# F1-chip.net
KiCad netlist of a schematic drawn in Altium Designer
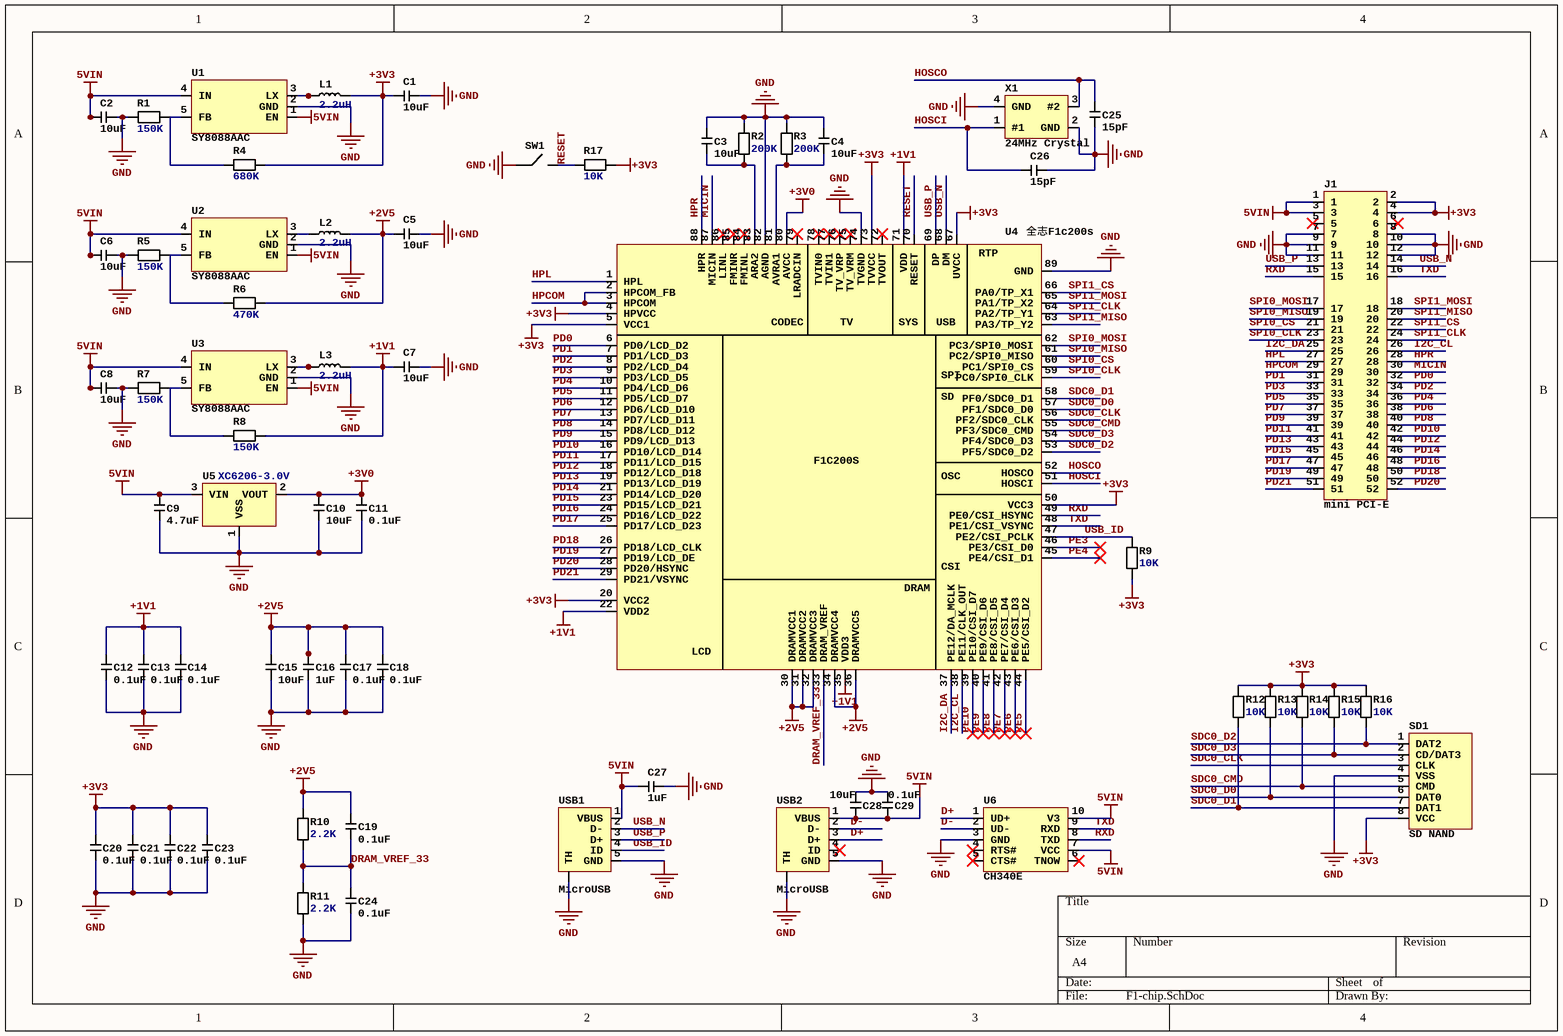
[diagram p0: F1-chip.SchDoc]

(export (version "E")
  (design (tool "Eeschema 10.0.6"))
  (components
    (comp (ref "C1")
      (value "10uF")
      (footprint "CAP_0402")
      (description "0402")
      (libsource (lib "myIntlib") (part "CAP_0402_10uF"))
    )
    (comp (ref "C2")
      (value "10uF")
      (footprint "CAP_0402")
      (description "0402")
      (libsource (lib "myIntlib") (part "CAP_0402_10uF"))
    )
    (comp (ref "C3")
      (value "10uF")
      (footprint "CAP_0402")
      (description "0402")
      (libsource (lib "myIntlib") (part "CAP_0402_10uF"))
    )
    (comp (ref "C4")
      (value "10uF")
      (footprint "CAP_0402")
      (description "0402")
      (libsource (lib "myIntlib") (part "CAP_0402_10uF"))
    )
    (comp (ref "C5")
      (value "10uF")
      (footprint "CAP_0402")
      (description "0402")
      (libsource (lib "myIntlib") (part "CAP_0402_10uF"))
    )
    (comp (ref "C6")
      (value "10uF")
      (footprint "CAP_0402")
      (description "0402")
      (libsource (lib "myIntlib") (part "CAP_0402_10uF"))
    )
    (comp (ref "C7")
      (value "10uF")
      (footprint "CAP_0402")
      (description "0402")
      (libsource (lib "myIntlib") (part "CAP_0402_10uF"))
    )
    (comp (ref "C8")
      (value "10uF")
      (footprint "CAP_0402")
      (description "0402")
      (libsource (lib "myIntlib") (part "CAP_0402_10uF"))
    )
    (comp (ref "C9")
      (value "4.7uF")
      (footprint "CAP_0402")
      (description "0402")
      (libsource (lib "myIntlib") (part "CAP_0402_4.7uF"))
    )
    (comp (ref "C10")
      (value "10uF")
      (footprint "CAP_0402")
      (description "0402")
      (libsource (lib "myIntlib") (part "CAP_0402_10uF"))
    )
    (comp (ref "C11")
      (value "0.1uF")
      (footprint "CAP_0402")
      (description "0402")
      (libsource (lib "myIntlib") (part "CAP_0402_0.1uF"))
    )
    (comp (ref "C12")
      (value "0.1uF")
      (footprint "CAP_0402")
      (description "0402")
      (libsource (lib "myIntlib") (part "CAP_0402_0.1uF"))
    )
    (comp (ref "C13")
      (value "0.1uF")
      (footprint "CAP_0402")
      (description "0402")
      (libsource (lib "myIntlib") (part "CAP_0402_0.1uF"))
    )
    (comp (ref "C14")
      (value "0.1uF")
      (footprint "CAP_0402")
      (description "0402")
      (libsource (lib "myIntlib") (part "CAP_0402_0.1uF"))
    )
    (comp (ref "C15")
      (value "10uF")
      (footprint "CAP_0402")
      (description "0402")
      (libsource (lib "myIntlib") (part "CAP_0402_10uF"))
    )
    (comp (ref "C16")
      (value "1uF")
      (footprint "CAP_0402")
      (description "0402")
      (libsource (lib "myIntlib") (part "CAP_0402_1uF"))
    )
    (comp (ref "C17")
      (value "0.1uF")
      (footprint "CAP_0402")
      (description "0402")
      (libsource (lib "myIntlib") (part "CAP_0402_0.1uF"))
    )
    (comp (ref "C18")
      (value "0.1uF")
      (footprint "CAP_0402")
      (description "0402")
      (libsource (lib "myIntlib") (part "CAP_0402_0.1uF"))
    )
    (comp (ref "C19")
      (value "0.1uF")
      (footprint "CAP_0402")
      (description "0402")
      (libsource (lib "myIntlib") (part "CAP_0402_0.1uF"))
    )
    (comp (ref "C20")
      (value "0.1uF")
      (footprint "CAP_0402")
      (description "0402")
      (libsource (lib "myIntlib") (part "CAP_0402_0.1uF"))
    )
    (comp (ref "C21")
      (value "0.1uF")
      (footprint "CAP_0402")
      (description "0402")
      (libsource (lib "myIntlib") (part "CAP_0402_0.1uF"))
    )
    (comp (ref "C22")
      (value "0.1uF")
      (footprint "CAP_0402")
      (description "0402")
      (libsource (lib "myIntlib") (part "CAP_0402_0.1uF"))
    )
    (comp (ref "C23")
      (value "0.1uF")
      (footprint "CAP_0402")
      (description "0402")
      (libsource (lib "myIntlib") (part "CAP_0402_0.1uF"))
    )
    (comp (ref "C24")
      (value "0.1uF")
      (footprint "CAP_0402")
      (description "0402")
      (libsource (lib "myIntlib") (part "CAP_0402_0.1uF"))
    )
    (comp (ref "C25")
      (value "15pF")
      (footprint "CAP_0402")
      (description "0402")
      (libsource (lib "myIntlib") (part "CAP_0402_15pF"))
    )
    (comp (ref "C26")
      (value "15pF")
      (footprint "CAP_0402")
      (description "0402")
      (libsource (lib "myIntlib") (part "CAP_0402_15pF"))
    )
    (comp (ref "C27")
      (value "1uF")
      (footprint "CAP_0402")
      (description "0402")
      (libsource (lib "myIntlib") (part "CAP_0402_1uF"))
    )
    (comp (ref "C28")
      (value "10uF")
      (footprint "CAP_0402")
      (description "0402")
      (libsource (lib "myIntlib") (part "CAP_0402_10uF"))
    )
    (comp (ref "C29")
      (value "0.1uF")
      (footprint "CAP_0402")
      (description "0402")
      (libsource (lib "myIntlib") (part "CAP_0402_0.1uF"))
    )
    (comp (ref "J1")
      (value "mini PCI-E")
      (footprint "mini PCI-E")
      (libsource (lib "myIntlib") (part "mini PCI-E"))
    )
    (comp (ref "L1")
      (value "2.2uH")
      (footprint "IND_0603")
      (description "0603")
      (libsource (lib "myIntlib") (part "IND_0603_2.2uH"))
    )
    (comp (ref "L2")
      (value "2.2uH")
      (footprint "IND_0603")
      (description "0603")
      (libsource (lib "myIntlib") (part "IND_0603_2.2uH"))
    )
    (comp (ref "L3")
      (value "2.2uH")
      (footprint "IND_0603")
      (description "0603")
      (libsource (lib "myIntlib") (part "IND_0603_2.2uH"))
    )
    (comp (ref "R1")
      (value "150K")
      (footprint "RES_0402")
      (description "0402")
      (libsource (lib "myIntlib") (part "RES_0402_150K"))
    )
    (comp (ref "R2")
      (value "200K")
      (footprint "RES_0402")
      (description "0402")
      (libsource (lib "myIntlib") (part "RES_0402_200K"))
    )
    (comp (ref "R3")
      (value "200K")
      (footprint "RES_0402")
      (description "0402")
      (libsource (lib "myIntlib") (part "RES_0402_200K"))
    )
    (comp (ref "R4")
      (value "680K")
      (footprint "RES_0402")
      (description "0402")
      (libsource (lib "myIntlib") (part "RES_0402_680K"))
    )
    (comp (ref "R5")
      (value "150K")
      (footprint "RES_0402")
      (description "0402")
      (libsource (lib "myIntlib") (part "RES_0402_150K"))
    )
    (comp (ref "R6")
      (value "470K")
      (footprint "RES_0402")
      (description "0402")
      (libsource (lib "myIntlib") (part "RES_0402_470K"))
    )
    (comp (ref "R7")
      (value "150K")
      (footprint "RES_0402")
      (description "0402")
      (libsource (lib "myIntlib") (part "RES_0402_150K"))
    )
    (comp (ref "R8")
      (value "150K")
      (footprint "RES_0402")
      (description "0402")
      (libsource (lib "myIntlib") (part "RES_0402_150K"))
    )
    (comp (ref "R9")
      (value "10K")
      (footprint "RES_0402")
      (description "0402")
      (libsource (lib "myIntlib") (part "RES_0402_10K"))
    )
    (comp (ref "R10")
      (value "2.2K")
      (footprint "RES_0402")
      (description "0402")
      (libsource (lib "myIntlib") (part "RES_0402_2.2K"))
    )
    (comp (ref "R11")
      (value "2.2K")
      (footprint "RES_0402")
      (description "0402")
      (libsource (lib "myIntlib") (part "RES_0402_2.2K"))
    )
    (comp (ref "R12")
      (value "10K")
      (footprint "RES_0402")
      (description "0402")
      (libsource (lib "myIntlib") (part "RES_0402_10K"))
    )
    (comp (ref "R13")
      (value "10K")
      (footprint "RES_0402")
      (description "0402")
      (libsource (lib "myIntlib") (part "RES_0402_10K"))
    )
    (comp (ref "R14")
      (value "10K")
      (footprint "RES_0402")
      (description "0402")
      (libsource (lib "myIntlib") (part "RES_0402_10K"))
    )
    (comp (ref "R15")
      (value "10K")
      (footprint "RES_0402")
      (description "0402")
      (libsource (lib "myIntlib") (part "RES_0402_10K"))
    )
    (comp (ref "R16")
      (value "10K")
      (footprint "RES_0402")
      (description "0402")
      (libsource (lib "myIntlib") (part "RES_0402_10K"))
    )
    (comp (ref "R17")
      (value "10K")
      (footprint "RES_0402")
      (description "0402")
      (libsource (lib "myIntlib") (part "RES_0402_10K"))
    )
    (comp (ref "SD1") (value "SD NAND") (footprint "SD NAND") (libsource (lib "myIntlib") (part "SD NAND")))
    (comp (ref "SW1")
      (value "贴片按钮")
      (footprint "BUTTON2")
      (description "3*4*2两脚小龟贴片按钮")
      (libsource (lib "myIntlib") (part "贴片按钮"))
    )
    (comp (ref "U1")
      (value "SY8088AAC")
      (footprint "SY8088AAC")
      (description "SOT23-5")
      (libsource (lib "myIntlib") (part "SY8088AAC"))
    )
    (comp (ref "U2")
      (value "SY8088AAC")
      (footprint "SY8088AAC")
      (description "SOT23-5")
      (libsource (lib "myIntlib") (part "SY8088AAC"))
    )
    (comp (ref "U3")
      (value "SY8088AAC")
      (footprint "SY8088AAC")
      (description "SOT23-5")
      (libsource (lib "myIntlib") (part "SY8088AAC"))
    )
    (comp (ref "U4")
      (value "全志F1c200s")
      (footprint "F1c200s")
      (description "MQFN-88")
      (libsource (lib "myIntlib") (part "F1c200s"))
    )
    (comp (ref "U5")
      (value "XC6206-3.0V")
      (footprint "XC6206")
      (description "SOT23-3")
      (libsource (lib "myIntlib") (part "XC6206-3.0V"))
    )
    (comp (ref "U6")
      (value "CH340E")
      (footprint "CH340E")
      (description "MSOP-10")
      (libsource (lib "myIntlib") (part "CH340E"))
    )
    (comp (ref "USB1")
      (value "MicroUSB")
      (footprint "MicroUSB")
      (libsource (lib "myIntlib") (part "MicroUSB"))
    )
    (comp (ref "USB2")
      (value "MicroUSB")
      (footprint "MicroUSB")
      (libsource (lib "myIntlib") (part "MicroUSB"))
    )
    (comp (ref "X1")
      (value "24MHz Crystal")
      (footprint "SMD3225")
      (description "SMD3225")
      (libsource (lib "myIntlib") (part "24MHz Crystal"))
    )
  )
  (nets
    (net (code "1") (name "+1V1") (class "Default")
      (node (ref "C12") (pin "2") (pinfunction "2_2") (pintype "passive"))
      (node (ref "C13") (pin "2") (pinfunction "2_2") (pintype "passive"))
      (node (ref "C14") (pin "2") (pinfunction "2_2") (pintype "passive"))
      (node (ref "C7") (pin "1") (pinfunction "1_1") (pintype "passive"))
      (node (ref "L3") (pin "2") (pinfunction "2_2") (pintype "passive"))
      (node (ref "R8") (pin "2") (pinfunction "2_2") (pintype "passive"))
      (node (ref "U4") (pin "22") (pinfunction "VDD2_22") (pintype "passive"))
      (node (ref "U4") (pin "35") (pinfunction "VDD3_35") (pintype "passive"))
      (node (ref "U4") (pin "71") (pinfunction "VDD_71") (pintype "passive"))
    )
    (net (code "2") (name "+2V5") (class "Default")
      (node (ref "C15") (pin "2") (pinfunction "2_2") (pintype "passive"))
      (node (ref "C16") (pin "2") (pinfunction "2_2") (pintype "passive"))
      (node (ref "C17") (pin "2") (pinfunction "2_2") (pintype "passive"))
      (node (ref "C18") (pin "2") (pinfunction "2_2") (pintype "passive"))
      (node (ref "C19") (pin "2") (pinfunction "2_2") (pintype "passive"))
      (node (ref "C5") (pin "1") (pinfunction "1_1") (pintype "passive"))
      (node (ref "L2") (pin "2") (pinfunction "2_2") (pintype "passive"))
      (node (ref "R10") (pin "2") (pinfunction "2_2") (pintype "passive"))
      (node (ref "R6") (pin "2") (pinfunction "2_2") (pintype "passive"))
      (node (ref "U4") (pin "30") (pinfunction "DRAMVCC1_30") (pintype "passive"))
      (node (ref "U4") (pin "31") (pinfunction "DRAMVCC2_31") (pintype "passive"))
      (node (ref "U4") (pin "32") (pinfunction "DRAMVCC3_32") (pintype "passive"))
      (node (ref "U4") (pin "34") (pinfunction "DRAMVCC4_34") (pintype "passive"))
      (node (ref "U4") (pin "36") (pinfunction "DRAMVCC5_36") (pintype "passive"))
    )
    (net (code "3") (name "+3V0") (class "Default")
      (node (ref "C10") (pin "2") (pinfunction "2_2") (pintype "passive"))
      (node (ref "C11") (pin "2") (pinfunction "2_2") (pintype "passive"))
      (node (ref "U4") (pin "80") (pinfunction "AVCC_80") (pintype "passive"))
      (node (ref "U5") (pin "2") (pinfunction "VOUT_2") (pintype "passive"))
    )
    (net (code "4") (name "+3V3") (class "Default")
      (node (ref "C1") (pin "1") (pinfunction "1_1") (pintype "passive"))
      (node (ref "C20") (pin "2") (pinfunction "2_2") (pintype "passive"))
      (node (ref "C21") (pin "2") (pinfunction "2_2") (pintype "passive"))
      (node (ref "C22") (pin "2") (pinfunction "2_2") (pintype "passive"))
      (node (ref "C23") (pin "2") (pinfunction "2_2") (pintype "passive"))
      (node (ref "J1") (pin "2") (pinfunction "2_2") (pintype "passive"))
      (node (ref "J1") (pin "4") (pinfunction "4_4") (pintype "passive"))
      (node (ref "L1") (pin "2") (pinfunction "2_2") (pintype "passive"))
      (node (ref "R12") (pin "2") (pinfunction "2_2") (pintype "passive"))
      (node (ref "R13") (pin "2") (pinfunction "2_2") (pintype "passive"))
      (node (ref "R14") (pin "2") (pinfunction "2_2") (pintype "passive"))
      (node (ref "R15") (pin "2") (pinfunction "2_2") (pintype "passive"))
      (node (ref "R16") (pin "2") (pinfunction "2_2") (pintype "passive"))
      (node (ref "R17") (pin "2") (pinfunction "2_2") (pintype "passive"))
      (node (ref "R4") (pin "2") (pinfunction "2_2") (pintype "passive"))
      (node (ref "R9") (pin "1") (pinfunction "1_1") (pintype "passive"))
      (node (ref "SD1") (pin "8") (pinfunction "VCC_8") (pintype "passive"))
      (node (ref "U4") (pin "20") (pinfunction "VCC2_20") (pintype "passive"))
      (node (ref "U4") (pin "4") (pinfunction "HPVCC_4") (pintype "passive"))
      (node (ref "U4") (pin "5") (pinfunction "VCC1_5") (pintype "passive"))
      (node (ref "U4") (pin "50") (pinfunction "VCC3_50") (pintype "passive"))
      (node (ref "U4") (pin "67") (pinfunction "UVCC_67") (pintype "passive"))
      (node (ref "U4") (pin "73") (pinfunction "TVVCC_73") (pintype "passive"))
    )
    (net (code "5") (name "/D+") (class "Default")
      (node (ref "U6") (pin "1") (pinfunction "UD+_1") (pintype "passive"))
      (node (ref "USB2") (pin "3") (pinfunction "D+_3") (pintype "passive"))
    )
    (net (code "6") (name "/D-") (class "Default")
      (node (ref "U6") (pin "2") (pinfunction "UD-_2") (pintype "passive"))
      (node (ref "USB2") (pin "2") (pinfunction "D-_2") (pintype "passive"))
    )
    (net (code "7") (name "/DRAM_VREF_33") (class "Default")
      (node (ref "C19") (pin "1") (pinfunction "1_1") (pintype "passive"))
      (node (ref "C24") (pin "2") (pinfunction "2_2") (pintype "passive"))
      (node (ref "R10") (pin "1") (pinfunction "1_1") (pintype "passive"))
      (node (ref "R11") (pin "2") (pinfunction "2_2") (pintype "passive"))
      (node (ref "U4") (pin "33") (pinfunction "DRAM_VREF_33") (pintype "passive"))
    )
    (net (code "8") (name "/HOSCI") (class "Default")
      (node (ref "C26") (pin "1") (pinfunction "1_1") (pintype "passive"))
      (node (ref "U4") (pin "51") (pinfunction "HOSCI_51") (pintype "passive"))
      (node (ref "X1") (pin "1") (pinfunction "#1_1") (pintype "passive"))
    )
    (net (code "9") (name "/HOSCO") (class "Default")
      (node (ref "C25") (pin "2") (pinfunction "2_2") (pintype "passive"))
      (node (ref "U4") (pin "52") (pinfunction "HOSCO_52") (pintype "passive"))
      (node (ref "X1") (pin "3") (pinfunction "#2_3") (pintype "passive"))
    )
    (net (code "10") (name "/HPCOM") (class "Default")
      (node (ref "J1") (pin "29") (pinfunction "29_29") (pintype "passive"))
      (node (ref "U4") (pin "2") (pinfunction "HPCOM_FB_2") (pintype "passive"))
      (node (ref "U4") (pin "3") (pinfunction "HPCOM_3") (pintype "passive"))
    )
    (net (code "11") (name "/HPL") (class "Default")
      (node (ref "J1") (pin "27") (pinfunction "27_27") (pintype "passive"))
      (node (ref "U4") (pin "1") (pinfunction "HPL_1") (pintype "passive"))
    )
    (net (code "12") (name "/HPR") (class "Default")
      (node (ref "J1") (pin "28") (pinfunction "28_28") (pintype "passive"))
      (node (ref "U4") (pin "88") (pinfunction "HPR_88") (pintype "passive"))
    )
    (net (code "13") (name "/I2C_CL") (class "Default")
      (node (ref "J1") (pin "26") (pinfunction "26_26") (pintype "passive"))
      (node (ref "U4") (pin "38") (pinfunction "PE11/CLK_OUT_38") (pintype "passive"))
    )
    (net (code "14") (name "/I2C_DA") (class "Default")
      (node (ref "J1") (pin "25") (pinfunction "25_25") (pintype "passive"))
      (node (ref "U4") (pin "37") (pinfunction "PE12/DA_MCLK_37") (pintype "passive"))
    )
    (net (code "15") (name "/MICIN") (class "Default")
      (node (ref "J1") (pin "30") (pinfunction "30_30") (pintype "passive"))
      (node (ref "U4") (pin "87") (pinfunction "MICIN_87") (pintype "passive"))
    )
    (net (code "16") (name "/PD0") (class "Default")
      (node (ref "J1") (pin "32") (pinfunction "32_32") (pintype "passive"))
      (node (ref "U4") (pin "6") (pinfunction "PD0/LCD_D2_6") (pintype "passive"))
    )
    (net (code "17") (name "/PD1") (class "Default")
      (node (ref "J1") (pin "31") (pinfunction "31_31") (pintype "passive"))
      (node (ref "U4") (pin "7") (pinfunction "PD1/LCD_D3_7") (pintype "passive"))
    )
    (net (code "18") (name "/PD2") (class "Default")
      (node (ref "J1") (pin "34") (pinfunction "34_34") (pintype "passive"))
      (node (ref "U4") (pin "8") (pinfunction "PD2/LCD_D4_8") (pintype "passive"))
    )
    (net (code "19") (name "/PD3") (class "Default")
      (node (ref "J1") (pin "33") (pinfunction "33_33") (pintype "passive"))
      (node (ref "U4") (pin "9") (pinfunction "PD3/LCD_D5_9") (pintype "passive"))
    )
    (net (code "20") (name "/PD4") (class "Default")
      (node (ref "J1") (pin "36") (pinfunction "36_36") (pintype "passive"))
      (node (ref "U4") (pin "10") (pinfunction "PD4/LCD_D6_10") (pintype "passive"))
    )
    (net (code "21") (name "/PD5") (class "Default")
      (node (ref "J1") (pin "35") (pinfunction "35_35") (pintype "passive"))
      (node (ref "U4") (pin "11") (pinfunction "PD5/LCD_D7_11") (pintype "passive"))
    )
    (net (code "22") (name "/PD6") (class "Default")
      (node (ref "J1") (pin "38") (pinfunction "38_38") (pintype "passive"))
      (node (ref "U4") (pin "12") (pinfunction "PD6/LCD_D10_12") (pintype "passive"))
    )
    (net (code "23") (name "/PD7") (class "Default")
      (node (ref "J1") (pin "37") (pinfunction "37_37") (pintype "passive"))
      (node (ref "U4") (pin "13") (pinfunction "PD7/LCD_D11_13") (pintype "passive"))
    )
    (net (code "24") (name "/PD8") (class "Default")
      (node (ref "J1") (pin "40") (pinfunction "40_40") (pintype "passive"))
      (node (ref "U4") (pin "14") (pinfunction "PD8/LCD_D12_14") (pintype "passive"))
    )
    (net (code "25") (name "/PD9") (class "Default")
      (node (ref "J1") (pin "39") (pinfunction "39_39") (pintype "passive"))
      (node (ref "U4") (pin "15") (pinfunction "PD9/LCD_D13_15") (pintype "passive"))
    )
    (net (code "26") (name "/PD10") (class "Default")
      (node (ref "J1") (pin "42") (pinfunction "42_42") (pintype "passive"))
      (node (ref "U4") (pin "16") (pinfunction "PD10/LCD_D14_16") (pintype "passive"))
    )
    (net (code "27") (name "/PD11") (class "Default")
      (node (ref "J1") (pin "41") (pinfunction "41_41") (pintype "passive"))
      (node (ref "U4") (pin "17") (pinfunction "PD11/LCD_D15_17") (pintype "passive"))
    )
    (net (code "28") (name "/PD12") (class "Default")
      (node (ref "J1") (pin "44") (pinfunction "44_44") (pintype "passive"))
      (node (ref "U4") (pin "18") (pinfunction "PD12/LCD_D18_18") (pintype "passive"))
    )
    (net (code "29") (name "/PD13") (class "Default")
      (node (ref "J1") (pin "43") (pinfunction "43_43") (pintype "passive"))
      (node (ref "U4") (pin "19") (pinfunction "PD13/LCD_D19_19") (pintype "passive"))
    )
    (net (code "30") (name "/PD14") (class "Default")
      (node (ref "J1") (pin "46") (pinfunction "46_46") (pintype "passive"))
      (node (ref "U4") (pin "21") (pinfunction "PD14/LCD_D20_21") (pintype "passive"))
    )
    (net (code "31") (name "/PD15") (class "Default")
      (node (ref "J1") (pin "45") (pinfunction "45_45") (pintype "passive"))
      (node (ref "U4") (pin "23") (pinfunction "PD15/LCD_D21_23") (pintype "passive"))
    )
    (net (code "32") (name "/PD16") (class "Default")
      (node (ref "J1") (pin "48") (pinfunction "48_48") (pintype "passive"))
      (node (ref "U4") (pin "24") (pinfunction "PD16/LCD_D22_24") (pintype "passive"))
    )
    (net (code "33") (name "/PD17") (class "Default")
      (node (ref "J1") (pin "47") (pinfunction "47_47") (pintype "passive"))
      (node (ref "U4") (pin "25") (pinfunction "PD17/LCD_D23_25") (pintype "passive"))
    )
    (net (code "34") (name "/PD18") (class "Default")
      (node (ref "J1") (pin "50") (pinfunction "50_50") (pintype "passive"))
      (node (ref "U4") (pin "26") (pinfunction "PD18/LCD_CLK_26") (pintype "passive"))
    )
    (net (code "35") (name "/PD19") (class "Default")
      (node (ref "J1") (pin "49") (pinfunction "49_49") (pintype "passive"))
      (node (ref "U4") (pin "27") (pinfunction "PD19/LCD_DE_27") (pintype "passive"))
    )
    (net (code "36") (name "/PD20") (class "Default")
      (node (ref "J1") (pin "52") (pinfunction "52_52") (pintype "passive"))
      (node (ref "U4") (pin "28") (pinfunction "PD20/HSYNC_28") (pintype "passive"))
    )
    (net (code "37") (name "/PD21") (class "Default")
      (node (ref "J1") (pin "51") (pinfunction "51_51") (pintype "passive"))
      (node (ref "U4") (pin "29") (pinfunction "PD21/VSYNC_29") (pintype "passive"))
    )
    (net (code "38") (name "/PE3") (class "Default")
      (node (ref "U4") (pin "46") (pinfunction "PE3/CSI_D0_46") (pintype "passive+no_connect"))
    )
    (net (code "39") (name "/PE4") (class "Default")
      (node (ref "U4") (pin "45") (pinfunction "PE4/CSI_D1_45") (pintype "passive+no_connect"))
    )
    (net (code "40") (name "/PE5") (class "Default")
      (node (ref "U4") (pin "44") (pinfunction "PE5/CSI_D2_44") (pintype "passive+no_connect"))
    )
    (net (code "41") (name "/PE6") (class "Default")
      (node (ref "U4") (pin "43") (pinfunction "PE6/CSI_D3_43") (pintype "passive+no_connect"))
    )
    (net (code "42") (name "/PE7") (class "Default")
      (node (ref "U4") (pin "42") (pinfunction "PE7/CSI_D4_42") (pintype "passive+no_connect"))
    )
    (net (code "43") (name "/PE8") (class "Default")
      (node (ref "U4") (pin "41") (pinfunction "PE8/CSI_D5_41") (pintype "passive+no_connect"))
    )
    (net (code "44") (name "/PE9") (class "Default")
      (node (ref "U4") (pin "40") (pinfunction "PE9/CSI_D6_40") (pintype "passive+no_connect"))
    )
    (net (code "45") (name "/PE10") (class "Default")
      (node (ref "U4") (pin "39") (pinfunction "PE10/CSI_D7_39") (pintype "passive+no_connect"))
    )
    (net (code "46") (name "/RESET") (class "Default")
      (node (ref "R17") (pin "1") (pinfunction "1_1") (pintype "passive"))
      (node (ref "SW1") (pin "2") (pintype "passive"))
      (node (ref "U4") (pin "70") (pinfunction "RESET_70") (pintype "passive"))
    )
    (net (code "47") (name "/RXD") (class "Default")
      (node (ref "J1") (pin "15") (pinfunction "15_15") (pintype "passive"))
      (node (ref "U4") (pin "49") (pinfunction "PE0/CSI_HSYNC_49") (pintype "passive"))
      (node (ref "U6") (pin "8") (pinfunction "TXD_8") (pintype "passive"))
    )
    (net (code "48") (name "/SDC0_CLK") (class "Default")
      (node (ref "SD1") (pin "3") (pinfunction "CLK_3") (pintype "passive"))
      (node (ref "U4") (pin "56") (pinfunction "PF2/SDC0_CLK_56") (pintype "passive"))
    )
    (net (code "49") (name "/SDC0_CMD") (class "Default")
      (node (ref "R14") (pin "1") (pinfunction "1_1") (pintype "passive"))
      (node (ref "SD1") (pin "5") (pinfunction "CMD_5") (pintype "passive"))
      (node (ref "U4") (pin "55") (pinfunction "PF3/SDC0_CMD_55") (pintype "passive"))
    )
    (net (code "50") (name "/SDC0_D0") (class "Default")
      (node (ref "R13") (pin "1") (pinfunction "1_1") (pintype "passive"))
      (node (ref "SD1") (pin "6") (pinfunction "DAT0_6") (pintype "passive"))
      (node (ref "U4") (pin "57") (pinfunction "PF1/SDC0_D0_57") (pintype "passive"))
    )
    (net (code "51") (name "/SDC0_D1") (class "Default")
      (node (ref "R12") (pin "1") (pinfunction "1_1") (pintype "passive"))
      (node (ref "SD1") (pin "7") (pinfunction "DAT1_7") (pintype "passive"))
      (node (ref "U4") (pin "58") (pinfunction "PF0/SDC0_D1_58") (pintype "passive"))
    )
    (net (code "52") (name "/SDC0_D2") (class "Default")
      (node (ref "R16") (pin "1") (pinfunction "1_1") (pintype "passive"))
      (node (ref "SD1") (pin "1") (pinfunction "DAT2_1") (pintype "passive"))
      (node (ref "U4") (pin "53") (pinfunction "PF5/SDC0_D2_53") (pintype "passive"))
    )
    (net (code "53") (name "/SDC0_D3") (class "Default")
      (node (ref "R15") (pin "1") (pinfunction "1_1") (pintype "passive"))
      (node (ref "SD1") (pin "2") (pinfunction "CD/DAT3_2") (pintype "passive"))
      (node (ref "U4") (pin "54") (pinfunction "PF4/SDC0_D3_54") (pintype "passive"))
    )
    (net (code "54") (name "/SPI0_CLK") (class "Default")
      (node (ref "J1") (pin "23") (pinfunction "23_23") (pintype "passive"))
      (node (ref "U4") (pin "59") (pinfunction "PC0/SPI0_CLK_59") (pintype "passive"))
    )
    (net (code "55") (name "/SPI0_CS") (class "Default")
      (node (ref "J1") (pin "21") (pinfunction "21_21") (pintype "passive"))
      (node (ref "U4") (pin "60") (pinfunction "PC1/SPI0_CS_60") (pintype "passive"))
    )
    (net (code "56") (name "/SPI0_MISO") (class "Default")
      (node (ref "J1") (pin "19") (pinfunction "19_19") (pintype "passive"))
      (node (ref "U4") (pin "61") (pinfunction "PC2/SPI0_MISO_61") (pintype "passive"))
    )
    (net (code "57") (name "/SPI0_MOSI") (class "Default")
      (node (ref "J1") (pin "17") (pinfunction "17_17") (pintype "passive"))
      (node (ref "U4") (pin "62") (pinfunction "PC3/SPI0_MOSI_62") (pintype "passive"))
    )
    (net (code "58") (name "/SPI1_CLK") (class "Default")
      (node (ref "J1") (pin "24") (pinfunction "24_24") (pintype "passive"))
      (node (ref "U4") (pin "64") (pinfunction "PA2/TP_Y1_64") (pintype "passive"))
    )
    (net (code "59") (name "/SPI1_CS") (class "Default")
      (node (ref "J1") (pin "22") (pinfunction "22_22") (pintype "passive"))
      (node (ref "U4") (pin "66") (pinfunction "PA0/TP_X1_66") (pintype "passive"))
    )
    (net (code "60") (name "/SPI1_MISO") (class "Default")
      (node (ref "J1") (pin "20") (pinfunction "20_20") (pintype "passive"))
      (node (ref "U4") (pin "63") (pinfunction "PA3/TP_Y2_63") (pintype "passive"))
    )
    (net (code "61") (name "/SPI1_MOSI") (class "Default")
      (node (ref "J1") (pin "18") (pinfunction "18_18") (pintype "passive"))
      (node (ref "U4") (pin "65") (pinfunction "PA1/TP_X2_65") (pintype "passive"))
    )
    (net (code "62") (name "/TXD") (class "Default")
      (node (ref "J1") (pin "16") (pinfunction "16_16") (pintype "passive"))
      (node (ref "U4") (pin "48") (pinfunction "PE1/CSI_VSYNC_48") (pintype "passive"))
      (node (ref "U6") (pin "9") (pinfunction "RXD_9") (pintype "passive"))
    )
    (net (code "63") (name "/USB_ID") (class "Default")
      (node (ref "R9") (pin "2") (pinfunction "2_2") (pintype "passive"))
      (node (ref "U4") (pin "47") (pinfunction "PE2/CSI_PCLK_47") (pintype "passive"))
      (node (ref "USB1") (pin "4") (pinfunction "ID_4") (pintype "passive"))
    )
    (net (code "64") (name "/USB_N") (class "Default")
      (node (ref "J1") (pin "14") (pinfunction "14_14") (pintype "passive"))
      (node (ref "U4") (pin "68") (pinfunction "DM_68") (pintype "passive"))
      (node (ref "USB1") (pin "2") (pinfunction "D-_2") (pintype "passive"))
    )
    (net (code "65") (name "/USB_P") (class "Default")
      (node (ref "J1") (pin "13") (pinfunction "13_13") (pintype "passive"))
      (node (ref "U4") (pin "69") (pinfunction "DP_69") (pintype "passive"))
      (node (ref "USB1") (pin "3") (pinfunction "D+_3") (pintype "passive"))
    )
    (net (code "66") (name "5VIN") (class "Default")
      (node (ref "C2") (pin "1") (pinfunction "1_1") (pintype "passive"))
      (node (ref "C27") (pin "1") (pinfunction "1_1") (pintype "passive"))
      (node (ref "C28") (pin "1") (pinfunction "1_1") (pintype "passive"))
      (node (ref "C29") (pin "1") (pinfunction "1_1") (pintype "passive"))
      (node (ref "C6") (pin "1") (pinfunction "1_1") (pintype "passive"))
      (node (ref "C8") (pin "1") (pinfunction "1_1") (pintype "passive"))
      (node (ref "C9") (pin "2") (pinfunction "2_2") (pintype "passive"))
      (node (ref "J1") (pin "1") (pinfunction "1_1") (pintype "passive"))
      (node (ref "J1") (pin "3") (pinfunction "3_3") (pintype "passive"))
      (node (ref "U1") (pin "1") (pinfunction "EN_1") (pintype "passive"))
      (node (ref "U1") (pin "4") (pinfunction "IN_4") (pintype "passive"))
      (node (ref "U2") (pin "1") (pinfunction "EN_1") (pintype "passive"))
      (node (ref "U2") (pin "4") (pinfunction "IN_4") (pintype "passive"))
      (node (ref "U3") (pin "1") (pinfunction "EN_1") (pintype "passive"))
      (node (ref "U3") (pin "4") (pinfunction "IN_4") (pintype "passive"))
      (node (ref "U5") (pin "3") (pinfunction "VIN_3") (pintype "passive"))
      (node (ref "U6") (pin "10") (pinfunction "V3_10") (pintype "passive"))
      (node (ref "U6") (pin "7") (pinfunction "VCC_7") (pintype "passive"))
      (node (ref "USB1") (pin "1") (pinfunction "VBUS_1") (pintype "passive"))
      (node (ref "USB2") (pin "1") (pinfunction "VBUS_1") (pintype "passive"))
    )
    (net (code "67") (name "GND") (class "Default")
      (node (ref "C1") (pin "2") (pinfunction "2_2") (pintype "passive"))
      (node (ref "C10") (pin "1") (pinfunction "1_1") (pintype "passive"))
      (node (ref "C11") (pin "1") (pinfunction "1_1") (pintype "passive"))
      (node (ref "C12") (pin "1") (pinfunction "1_1") (pintype "passive"))
      (node (ref "C13") (pin "1") (pinfunction "1_1") (pintype "passive"))
      (node (ref "C14") (pin "1") (pinfunction "1_1") (pintype "passive"))
      (node (ref "C15") (pin "1") (pinfunction "1_1") (pintype "passive"))
      (node (ref "C16") (pin "1") (pinfunction "1_1") (pintype "passive"))
      (node (ref "C17") (pin "1") (pinfunction "1_1") (pintype "passive"))
      (node (ref "C18") (pin "1") (pinfunction "1_1") (pintype "passive"))
      (node (ref "C2") (pin "2") (pinfunction "2_2") (pintype "passive"))
      (node (ref "C20") (pin "1") (pinfunction "1_1") (pintype "passive"))
      (node (ref "C21") (pin "1") (pinfunction "1_1") (pintype "passive"))
      (node (ref "C22") (pin "1") (pinfunction "1_1") (pintype "passive"))
      (node (ref "C23") (pin "1") (pinfunction "1_1") (pintype "passive"))
      (node (ref "C24") (pin "1") (pinfunction "1_1") (pintype "passive"))
      (node (ref "C25") (pin "1") (pinfunction "1_1") (pintype "passive"))
      (node (ref "C26") (pin "2") (pinfunction "2_2") (pintype "passive"))
      (node (ref "C27") (pin "2") (pinfunction "2_2") (pintype "passive"))
      (node (ref "C28") (pin "2") (pinfunction "2_2") (pintype "passive"))
      (node (ref "C29") (pin "2") (pinfunction "2_2") (pintype "passive"))
      (node (ref "C3") (pin "2") (pinfunction "2_2") (pintype "passive"))
      (node (ref "C4") (pin "2") (pinfunction "2_2") (pintype "passive"))
      (node (ref "C5") (pin "2") (pinfunction "2_2") (pintype "passive"))
      (node (ref "C6") (pin "2") (pinfunction "2_2") (pintype "passive"))
      (node (ref "C7") (pin "2") (pinfunction "2_2") (pintype "passive"))
      (node (ref "C8") (pin "2") (pinfunction "2_2") (pintype "passive"))
      (node (ref "C9") (pin "1") (pinfunction "1_1") (pintype "passive"))
      (node (ref "J1") (pin "10") (pinfunction "10_10") (pintype "passive"))
      (node (ref "J1") (pin "11") (pinfunction "11_11") (pintype "passive"))
      (node (ref "J1") (pin "12") (pinfunction "12_12") (pintype "passive"))
      (node (ref "J1") (pin "7") (pinfunction "7_7") (pintype "passive"))
      (node (ref "J1") (pin "8") (pinfunction "8_8") (pintype "passive"))
      (node (ref "J1") (pin "9") (pinfunction "9_9") (pintype "passive"))
      (node (ref "R1") (pin "1") (pinfunction "1_1") (pintype "passive"))
      (node (ref "R11") (pin "1") (pinfunction "1_1") (pintype "passive"))
      (node (ref "R2") (pin "2") (pinfunction "2_2") (pintype "passive"))
      (node (ref "R3") (pin "2") (pinfunction "2_2") (pintype "passive"))
      (node (ref "R5") (pin "1") (pinfunction "1_1") (pintype "passive"))
      (node (ref "R7") (pin "1") (pinfunction "1_1") (pintype "passive"))
      (node (ref "SD1") (pin "4") (pinfunction "VSS_4") (pintype "passive"))
      (node (ref "SW1") (pin "1") (pintype "passive"))
      (node (ref "U1") (pin "2") (pinfunction "GND_2") (pintype "passive"))
      (node (ref "U2") (pin "2") (pinfunction "GND_2") (pintype "passive"))
      (node (ref "U3") (pin "2") (pinfunction "GND_2") (pintype "passive"))
      (node (ref "U4") (pin "74") (pinfunction "TVGND_74") (pintype "passive"))
      (node (ref "U4") (pin "82") (pinfunction "AGND_82") (pintype "passive"))
      (node (ref "U4") (pin "89") (pinfunction "GND_89") (pintype "passive"))
      (node (ref "U5") (pin "1") (pinfunction "VSS_1") (pintype "passive"))
      (node (ref "U6") (pin "3") (pinfunction "GND_3") (pintype "passive"))
      (node (ref "USB1") (pin "0") (pinfunction "TH_0") (pintype "passive"))
      (node (ref "USB1") (pin "5") (pinfunction "GND_5") (pintype "passive"))
      (node (ref "USB2") (pin "0") (pinfunction "TH_0") (pintype "passive"))
      (node (ref "USB2") (pin "5") (pinfunction "GND_5") (pintype "passive"))
      (node (ref "X1") (pin "2") (pinfunction "GND_2") (pintype "passive"))
      (node (ref "X1") (pin "4") (pinfunction "GND_4") (pintype "passive"))
    )
    (net (code "68") (name "Net-(U1-FB)") (class "Default")
      (node (ref "R1") (pin "2") (pinfunction "2_2") (pintype "passive"))
      (node (ref "R4") (pin "1") (pinfunction "1_1") (pintype "passive"))
      (node (ref "U1") (pin "5") (pinfunction "FB_5") (pintype "passive"))
    )
    (net (code "69") (name "Net-(U1-LX)") (class "Default")
      (node (ref "L1") (pin "1") (pinfunction "1_1") (pintype "passive"))
      (node (ref "U1") (pin "3") (pinfunction "LX_3") (pintype "passive"))
    )
    (net (code "70") (name "Net-(U2-FB)") (class "Default")
      (node (ref "R5") (pin "2") (pinfunction "2_2") (pintype "passive"))
      (node (ref "R6") (pin "1") (pinfunction "1_1") (pintype "passive"))
      (node (ref "U2") (pin "5") (pinfunction "FB_5") (pintype "passive"))
    )
    (net (code "71") (name "Net-(U2-LX)") (class "Default")
      (node (ref "L2") (pin "1") (pinfunction "1_1") (pintype "passive"))
      (node (ref "U2") (pin "3") (pinfunction "LX_3") (pintype "passive"))
    )
    (net (code "72") (name "Net-(U3-FB)") (class "Default")
      (node (ref "R7") (pin "2") (pinfunction "2_2") (pintype "passive"))
      (node (ref "R8") (pin "1") (pinfunction "1_1") (pintype "passive"))
      (node (ref "U3") (pin "5") (pinfunction "FB_5") (pintype "passive"))
    )
    (net (code "73") (name "Net-(U3-LX)") (class "Default")
      (node (ref "L3") (pin "1") (pinfunction "1_1") (pintype "passive"))
      (node (ref "U3") (pin "3") (pinfunction "LX_3") (pintype "passive"))
    )
    (net (code "74") (name "Net-(U4-ARA2)") (class "Default")
      (node (ref "C3") (pin "1") (pinfunction "1_1") (pintype "passive"))
      (node (ref "R2") (pin "1") (pinfunction "1_1") (pintype "passive"))
      (node (ref "U4") (pin "83") (pinfunction "ARA2_83") (pintype "passive"))
    )
    (net (code "75") (name "Net-(U4-AVRA1)") (class "Default")
      (node (ref "C4") (pin "1") (pinfunction "1_1") (pintype "passive"))
      (node (ref "R3") (pin "1") (pinfunction "1_1") (pintype "passive"))
      (node (ref "U4") (pin "81") (pinfunction "AVRA1_81") (pintype "passive"))
    )
    (net (code "76") (name "unconnected-(J1-Pad5)") (class "Default")
      (node (ref "J1") (pin "5") (pinfunction "5_5") (pintype "passive+no_connect"))
    )
    (net (code "77") (name "unconnected-(J1-Pad6)") (class "Default")
      (node (ref "J1") (pin "6") (pinfunction "6_6") (pintype "passive+no_connect"))
    )
    (net (code "78") (name "unconnected-(U4-FMINL-Pad84)") (class "Default")
      (node (ref "U4") (pin "84") (pinfunction "FMINL_84") (pintype "passive+no_connect"))
    )
    (net (code "79") (name "unconnected-(U4-FMINR-Pad85)") (class "Default")
      (node (ref "U4") (pin "85") (pinfunction "FMINR_85") (pintype "passive+no_connect"))
    )
    (net (code "80") (name "unconnected-(U4-LINL-Pad86)") (class "Default")
      (node (ref "U4") (pin "86") (pinfunction "LINL_86") (pintype "passive+no_connect"))
    )
    (net (code "81") (name "unconnected-(U4-LRADCIN-Pad79)") (class "Default")
      (node (ref "U4") (pin "79") (pinfunction "LRADCIN_79") (pintype "passive+no_connect"))
    )
    (net (code "82") (name "unconnected-(U4-TVIN0-Pad78)") (class "Default")
      (node (ref "U4") (pin "78") (pinfunction "TVIN0_78") (pintype "passive+no_connect"))
    )
    (net (code "83") (name "unconnected-(U4-TVIN1-Pad77)") (class "Default")
      (node (ref "U4") (pin "77") (pinfunction "TVIN1_77") (pintype "passive+no_connect"))
    )
    (net (code "84") (name "unconnected-(U4-TVOUT-Pad72)") (class "Default")
      (node (ref "U4") (pin "72") (pinfunction "TVOUT_72") (pintype "passive+no_connect"))
    )
    (net (code "85") (name "unconnected-(U4-TV_VRM-Pad75)") (class "Default")
      (node (ref "U4") (pin "75") (pinfunction "TV_VRM_75") (pintype "passive+no_connect"))
    )
    (net (code "86") (name "unconnected-(U4-TV_VRP-Pad76)") (class "Default")
      (node (ref "U4") (pin "76") (pinfunction "TV_VRP_76") (pintype "passive+no_connect"))
    )
    (net (code "87") (name "unconnected-(U6-CTS#-Pad5)") (class "Default")
      (node (ref "U6") (pin "5") (pinfunction "CTS#_5") (pintype "passive+no_connect"))
    )
    (net (code "88") (name "unconnected-(U6-RTS#-Pad4)") (class "Default")
      (node (ref "U6") (pin "4") (pinfunction "RTS#_4") (pintype "passive+no_connect"))
    )
    (net (code "89") (name "unconnected-(U6-TNOW-Pad6)") (class "Default")
      (node (ref "U6") (pin "6") (pinfunction "TNOW_6") (pintype "passive+no_connect"))
    )
    (net (code "90") (name "unconnected-(USB2-ID-Pad4)") (class "Default")
      (node (ref "USB2") (pin "4") (pinfunction "ID_4") (pintype "passive+no_connect"))
    )
  )
)
